# RCMX_Rev_00_BPS2.net
KiCad netlist of a schematic drawn in EAGLE
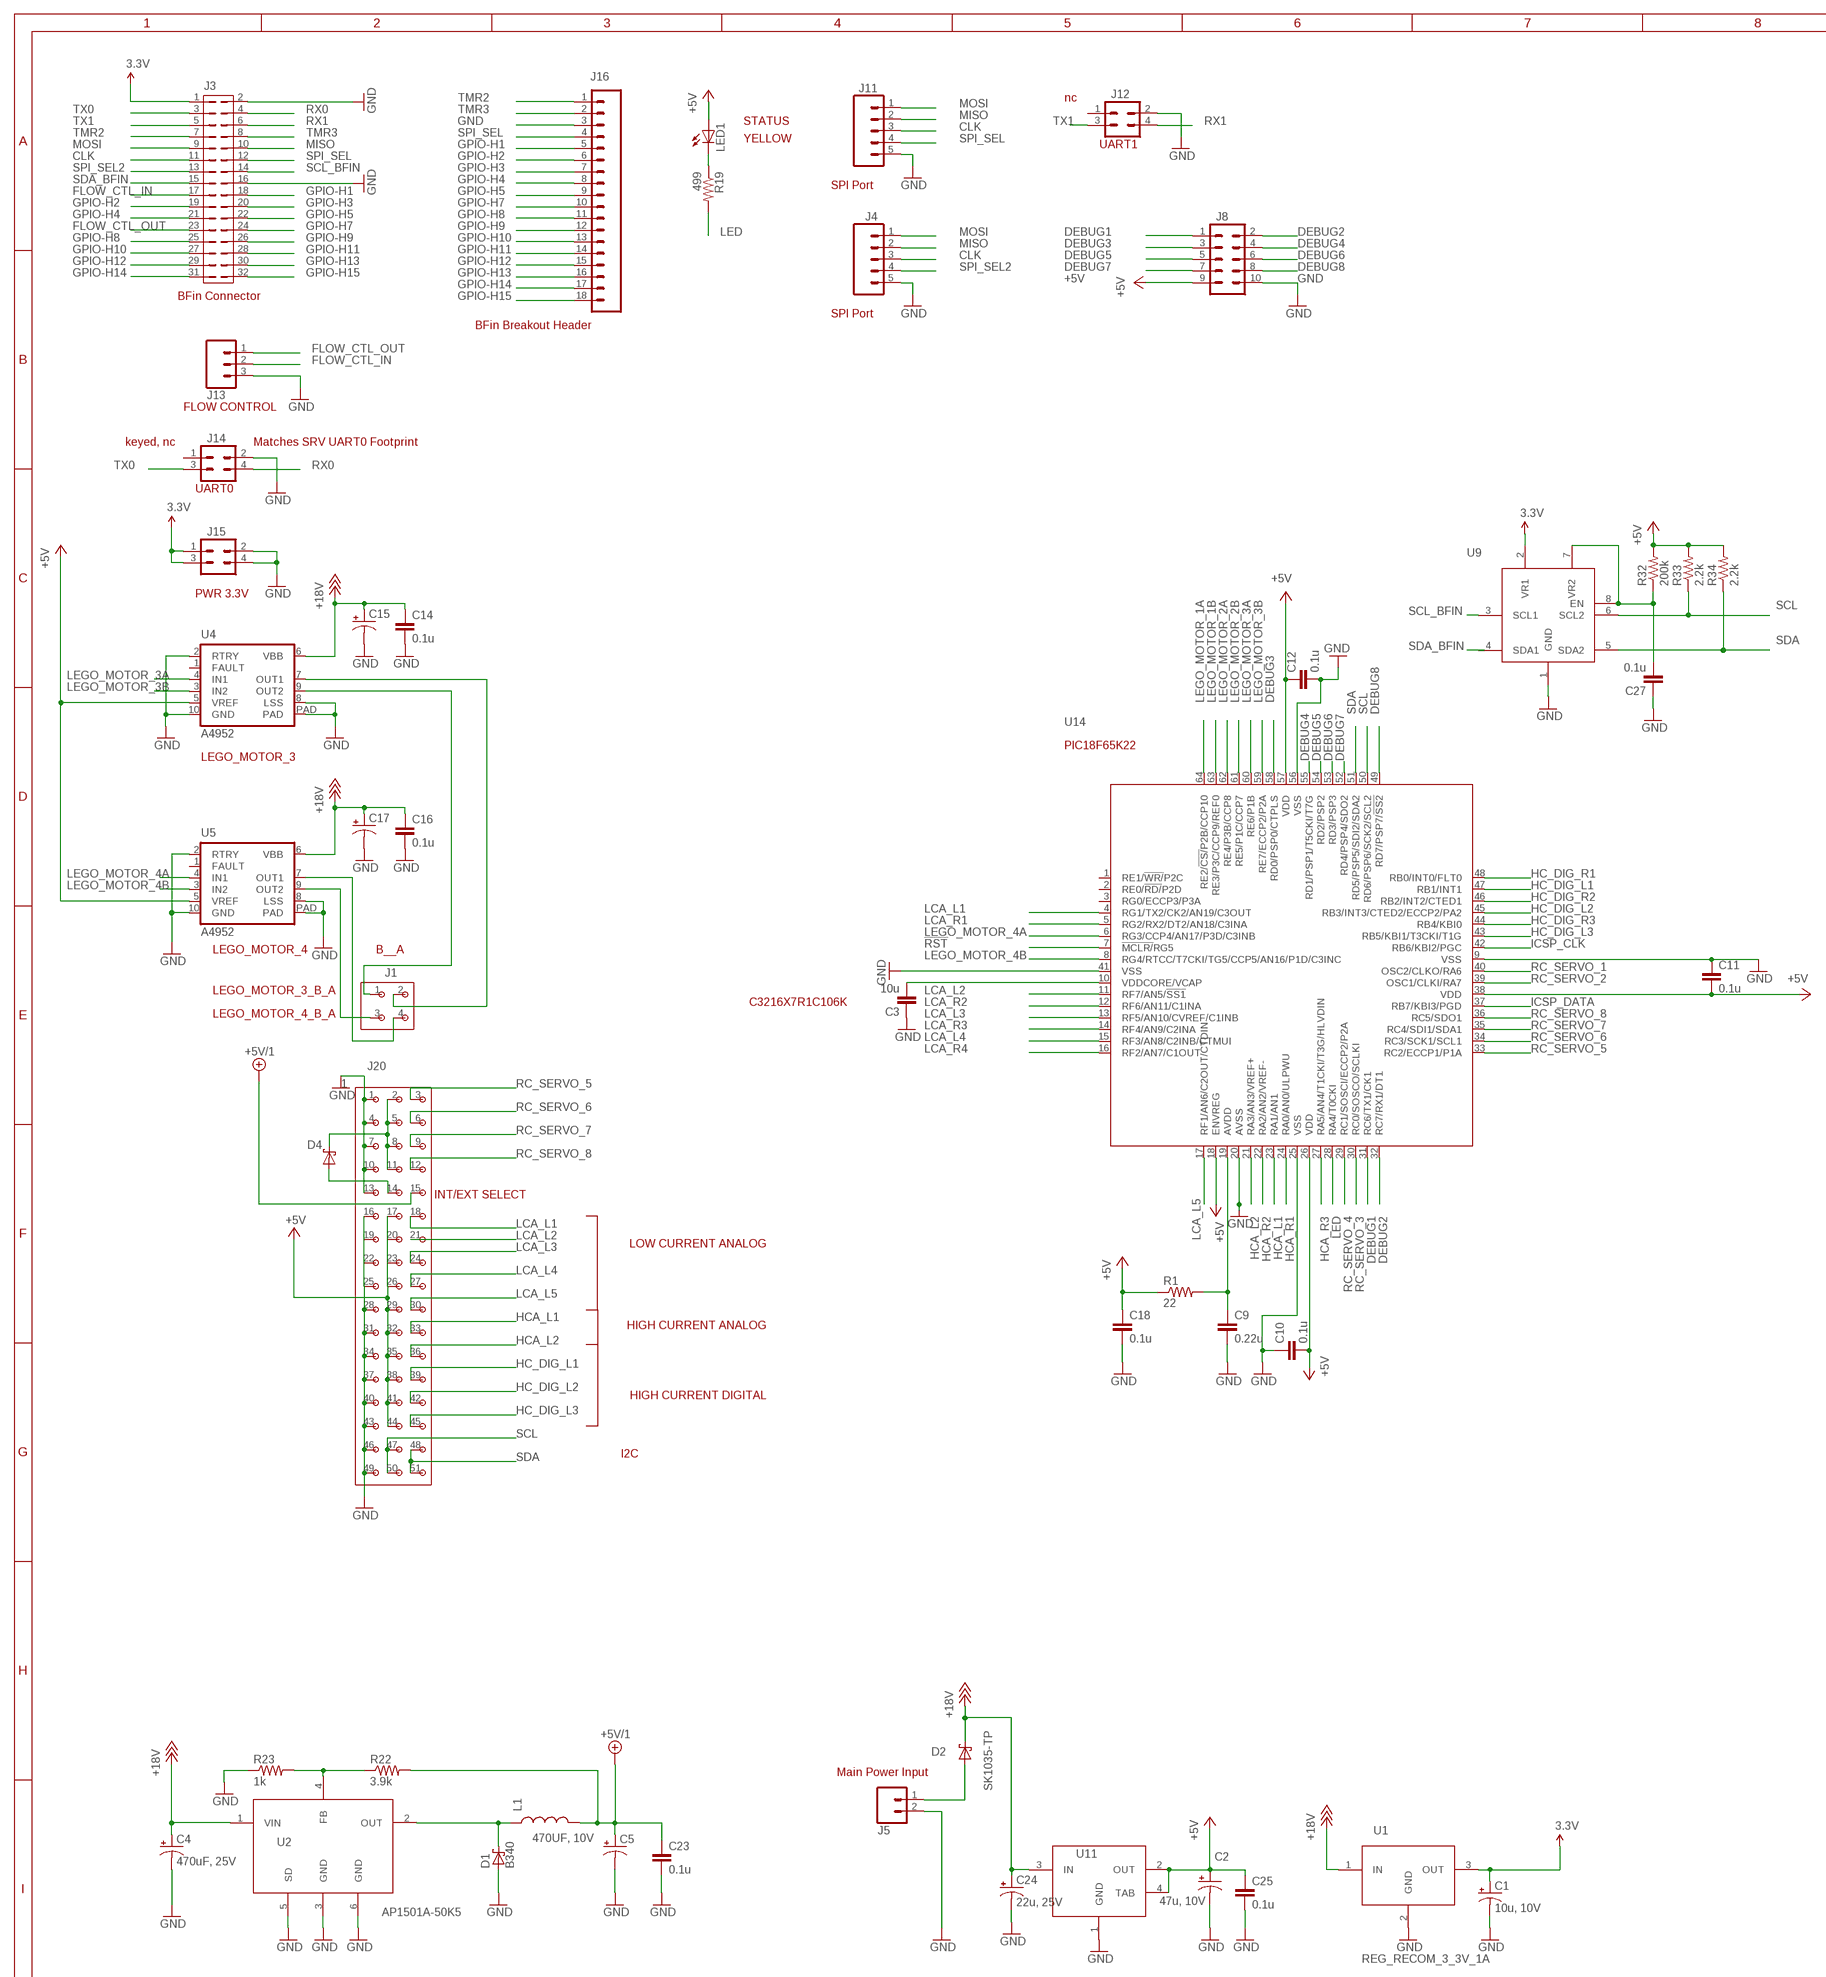
[diagram p0: schematic, sheet 1, part 1 of 2]
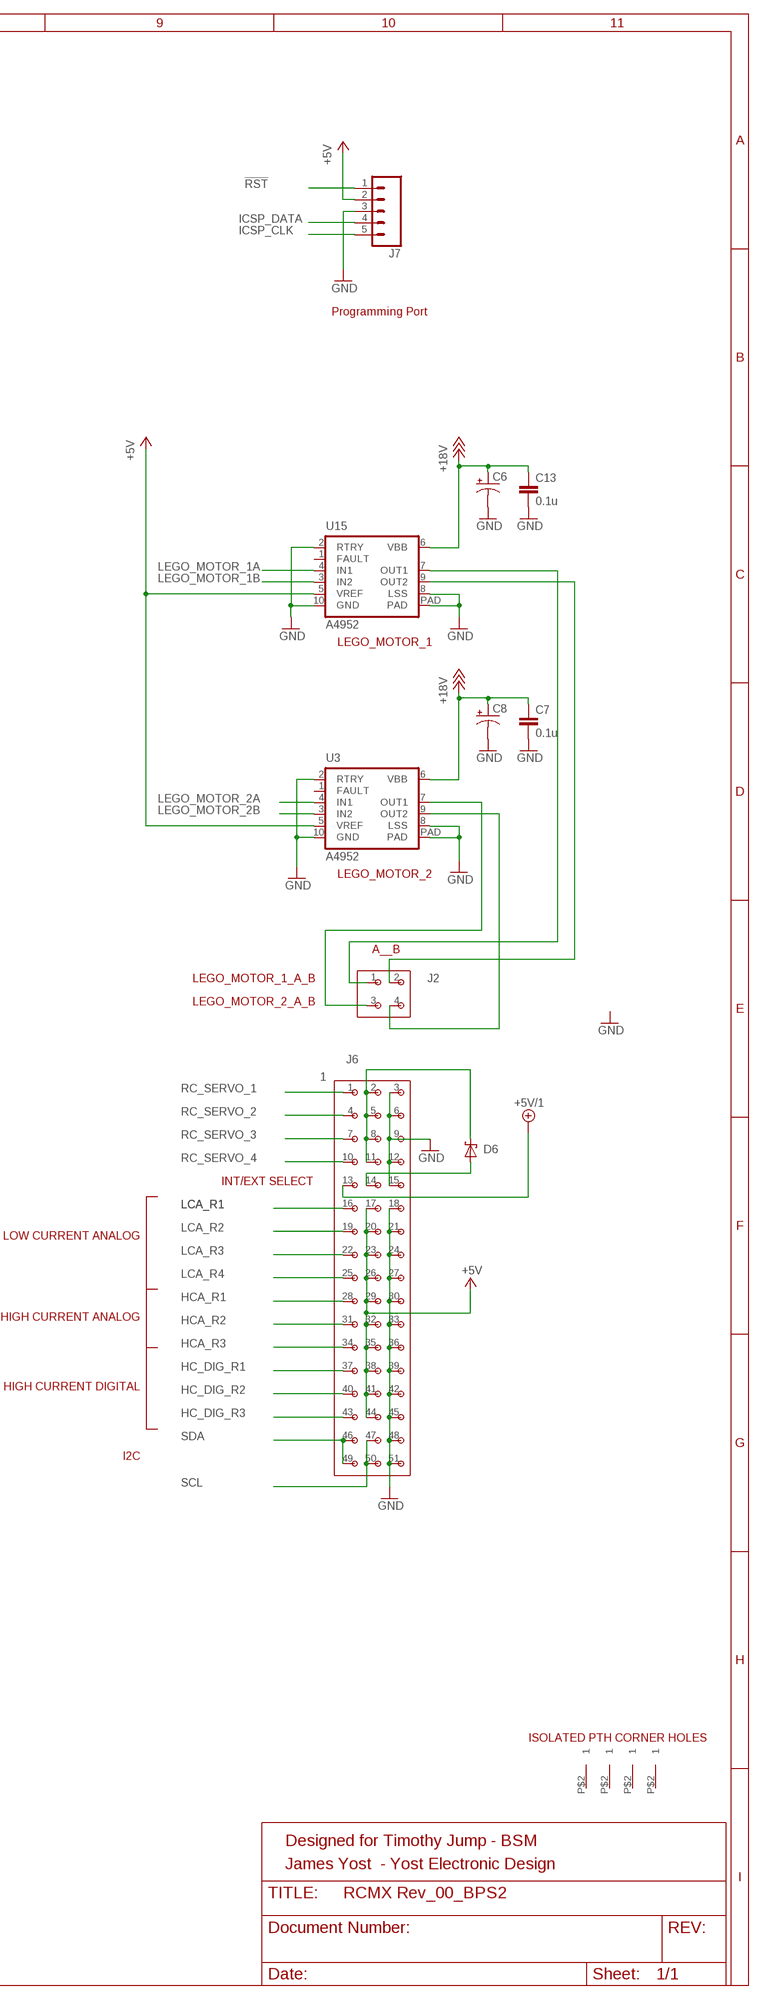
[diagram p1: schematic, sheet 1, part 2 of 2]

(export (version "E")
  (design (tool "Eeschema 10.0.6"))
  (components
    (comp (ref "C1")
      (value "10u, 10V")
      (footprint "eagle-import:EIA3216")
      (libsource (lib "eagle-import") (part "CAP_POL1206"))
    )
    (comp (ref "C2")
      (value "47u, 10V")
      (footprint "eagle-import:CAP1210_POL")
      (libsource (lib "eagle-import") (part "CAP_1210_POL"))
    )
    (comp (ref "C3")
      (value "10u")
      (footprint "eagle-import:1206")
      (libsource (lib "eagle-import") (part "CAP1206"))
    )
    (comp (ref "C4")
      (value "470uF, 25V")
      (footprint "eagle-import:PANASONIC_G")
      (libsource (lib "eagle-import") (part "CAP_POLG"))
    )
    (comp (ref "C5")
      (value "470UF, 10V")
      (footprint "eagle-import:PANASONIC_F")
      (libsource (lib "eagle-import") (part "CAP_ELT_PANASONIC_470UF"))
    )
    (comp (ref "C6")
      (value "CAP_POLD")
      (footprint "eagle-import:PANASONIC_D")
      (libsource (lib "eagle-import") (part "CAP_POLD"))
    )
    (comp (ref "C7")
      (value "0.1u")
      (footprint "eagle-import:0805")
      (libsource (lib "eagle-import") (part "CAP0805"))
    )
    (comp (ref "C8")
      (value "CAP_POLD")
      (footprint "eagle-import:PANASONIC_D")
      (libsource (lib "eagle-import") (part "CAP_POLD"))
    )
    (comp (ref "C9")
      (value "0.22u")
      (footprint "eagle-import:0805")
      (libsource (lib "eagle-import") (part "CAP0805"))
    )
    (comp (ref "C10")
      (value "0.1u")
      (footprint "eagle-import:0805")
      (libsource (lib "eagle-import") (part "CAP0805"))
    )
    (comp (ref "C11")
      (value "0.1u")
      (footprint "eagle-import:0805")
      (libsource (lib "eagle-import") (part "CAP0805"))
    )
    (comp (ref "C12")
      (value "0.1u")
      (footprint "eagle-import:0805")
      (libsource (lib "eagle-import") (part "CAP0805"))
    )
    (comp (ref "C13")
      (value "0.1u")
      (footprint "eagle-import:0805")
      (libsource (lib "eagle-import") (part "CAP0805"))
    )
    (comp (ref "C14")
      (value "0.1u")
      (footprint "eagle-import:0805")
      (libsource (lib "eagle-import") (part "CAP0805"))
    )
    (comp (ref "C15")
      (value "CAP_POLD")
      (footprint "eagle-import:PANASONIC_D")
      (libsource (lib "eagle-import") (part "CAP_POLD"))
    )
    (comp (ref "C16")
      (value "0.1u")
      (footprint "eagle-import:0805")
      (libsource (lib "eagle-import") (part "CAP0805"))
    )
    (comp (ref "C17")
      (value "CAP_POLD")
      (footprint "eagle-import:PANASONIC_D")
      (libsource (lib "eagle-import") (part "CAP_POLD"))
    )
    (comp (ref "C18")
      (value "0.1u")
      (footprint "eagle-import:0805")
      (libsource (lib "eagle-import") (part "CAP0805"))
    )
    (comp (ref "C23")
      (value "0.1u")
      (footprint "eagle-import:0805")
      (libsource (lib "eagle-import") (part "CAP0805"))
    )
    (comp (ref "C24")
      (value "22u, 25V")
      (footprint "eagle-import:CAP1210_POL")
      (libsource (lib "eagle-import") (part "CAP_1210_POL"))
    )
    (comp (ref "C25")
      (value "0.1u")
      (footprint "eagle-import:0805")
      (libsource (lib "eagle-import") (part "CAP0805"))
    )
    (comp (ref "C27")
      (value "0.1u")
      (footprint "eagle-import:0805")
      (libsource (lib "eagle-import") (part "CAP0805"))
    )
    (comp (ref "D1")
      (value "B340")
      (footprint "eagle-import:SMA_DO214AC")
      (libsource (lib "eagle-import") (part "B340"))
    )
    (comp (ref "D2")
      (value "SK1035-TP")
      (footprint "eagle-import:DO214AB")
      (libsource (lib "eagle-import") (part "SK1035-TP"))
    )
    (comp (ref "D4")
      (value "SK1035-TP")
      (footprint "eagle-import:DO214AB")
      (libsource (lib "eagle-import") (part "SK1035-TP"))
    )
    (comp (ref "D6")
      (value "SK1035-TP")
      (footprint "eagle-import:DO214AB")
      (libsource (lib "eagle-import") (part "SK1035-TP"))
    )
    (comp (ref "J1")
      (value "CON_2X2_0_100")
      (footprint "eagle-import:CON_2X2_0_100")
      (libsource (lib "eagle-import") (part "CON_2X2_0_100"))
    )
    (comp (ref "J2")
      (value "CON_2X2_0_100")
      (footprint "eagle-import:CON_2X2_0_100")
      (libsource (lib "eagle-import") (part "CON_2X2_0_100"))
    )
    (comp (ref "J3")
      (value "CON_2X16_0_100")
      (footprint "eagle-import:CON_2X16_0_100")
      (libsource (lib "eagle-import") (part "CON_2X16_0_100"))
    )
    (comp (ref "J4")
      (value "M05PTH")
      (footprint "eagle-import:1X05")
      (libsource (lib "eagle-import") (part "M05PTH"))
    )
    (comp (ref "J5")
      (value "M02NG")
      (footprint "eagle-import:1X02")
      (libsource (lib "eagle-import") (part "M02NG"))
    )
    (comp (ref "J6")
      (value "CON_3X17_0_100")
      (footprint "eagle-import:CON_3X17_0_100")
      (libsource (lib "eagle-import") (part "CON_3X17_0_100"))
    )
    (comp (ref "J7")
      (value "M05PTH")
      (footprint "eagle-import:1X05")
      (libsource (lib "eagle-import") (part "SparkFun-Connectors_M05PTH"))
    )
    (comp (ref "J8")
      (value "M05X2PTH")
      (footprint "eagle-import:AVR_ICSP")
      (libsource (lib "eagle-import") (part "M05X2PTH"))
    )
    (comp (ref "J11")
      (value "M05PTH")
      (footprint "eagle-import:1X05")
      (libsource (lib "eagle-import") (part "M05PTH"))
    )
    (comp (ref "J12")
      (value "CON2X2")
      (footprint "eagle-import:CON2X2")
      (libsource (lib "eagle-import") (part "CON2X2"))
    )
    (comp (ref "J13")
      (value "M03PTH")
      (footprint "eagle-import:1X03")
      (libsource (lib "eagle-import") (part "M03PTH"))
    )
    (comp (ref "J14")
      (value "CON2X2")
      (footprint "eagle-import:CON2X2")
      (libsource (lib "eagle-import") (part "CON2X2"))
    )
    (comp (ref "J15")
      (value "CON2X2")
      (footprint "eagle-import:CON2X2")
      (libsource (lib "eagle-import") (part "CON2X2"))
    )
    (comp (ref "J16")
      (value "CON1X18")
      (footprint "eagle-import:CON1X18")
      (libsource (lib "eagle-import") (part "CON1X18"))
    )
    (comp (ref "J20")
      (value "CON_3X17_0_100")
      (footprint "eagle-import:CON_3X17_0_100")
      (libsource (lib "eagle-import") (part "CON_3X17_0_100"))
    )
    (comp (ref "L1")
      (value "IND_47UH_COILTRONICS_2_95A")
      (footprint "eagle-import:IND_PADS_SMT")
      (libsource (lib "eagle-import") (part "IND_47UH_COILTRONICS_2_95A"))
    )
    (comp (ref "LED1")
      (value "LEDCHIP-LED0805")
      (footprint "eagle-import:CHIP-LED0805")
      (libsource (lib "eagle-import") (part "LEDCHIP-LED0805"))
    )
    (comp (ref "R1")
      (value "22")
      (footprint "eagle-import:0805")
      (libsource (lib "eagle-import") (part "RESISTOR"))
    )
    (comp (ref "R19")
      (value "499")
      (footprint "eagle-import:0805")
      (libsource (lib "eagle-import") (part "RESISTOR"))
    )
    (comp (ref "R22")
      (value "3.9k")
      (footprint "eagle-import:0805")
      (libsource (lib "eagle-import") (part "RESISTOR"))
    )
    (comp (ref "R23")
      (value "1k")
      (footprint "eagle-import:0805")
      (libsource (lib "eagle-import") (part "RESISTOR"))
    )
    (comp (ref "R32")
      (value "200k")
      (footprint "eagle-import:0805")
      (libsource (lib "eagle-import") (part "RESISTOR"))
    )
    (comp (ref "R33")
      (value "2.2k")
      (footprint "eagle-import:0805")
      (libsource (lib "eagle-import") (part "RESISTOR"))
    )
    (comp (ref "R34")
      (value "2.2k")
      (footprint "eagle-import:0805")
      (libsource (lib "eagle-import") (part "RESISTOR"))
    )
    (comp (ref "U$1")
      (value "GNDPAD")
      (footprint "eagle-import:GNDPAD")
      (libsource (lib "eagle-import") (part "GNDPAD"))
    )
    (comp (ref "U$2")
      (value "GNDPAD")
      (footprint "eagle-import:GNDPAD")
      (libsource (lib "eagle-import") (part "GNDPAD"))
    )
    (comp (ref "U$7")
      (value "GNDPAD")
      (footprint "eagle-import:GNDPAD")
      (libsource (lib "eagle-import") (part "GNDPAD"))
    )
    (comp (ref "U$8")
      (value "GNDPAD")
      (footprint "eagle-import:GNDPAD")
      (libsource (lib "eagle-import") (part "GNDPAD"))
    )
    (comp (ref "U1")
      (value "REG_RECOM_3_3V_1A")
      (footprint "eagle-import:REG_RECOM_3_3V_1A")
      (libsource (lib "eagle-import") (part "REG_RECOM_3_3V_1A"))
    )
    (comp (ref "U2")
      (value "AP1501A-50K5")
      (footprint "eagle-import:TO263-5")
      (libsource (lib "eagle-import") (part "AP1501A-50K5"))
    )
    (comp (ref "U3")
      (value "A4952")
      (footprint "eagle-import:MSOP10_W_THERMAL_PAD")
      (libsource (lib "eagle-import") (part "A4952"))
    )
    (comp (ref "U4")
      (value "A4952")
      (footprint "eagle-import:MSOP10_W_THERMAL_PAD")
      (libsource (lib "eagle-import") (part "A4952"))
    )
    (comp (ref "U5")
      (value "A4952")
      (footprint "eagle-import:MSOP10_W_THERMAL_PAD")
      (libsource (lib "eagle-import") (part "A4952"))
    )
    (comp (ref "U9")
      (value "PCA9306DCT")
      (footprint "eagle-import:TEST08")
      (libsource (lib "eagle-import") (part "PCA9306DCT"))
    )
    (comp (ref "U11")
      (value "TLV1117-5")
      (footprint "eagle-import:SOT223")
      (libsource (lib "eagle-import") (part "TLV1117-5"))
    )
    (comp (ref "U14")
      (value "MICRO_C_PIC18F65K22")
      (footprint "eagle-import:64PIN_TQFP_10X10X1MM")
      (libsource (lib "eagle-import") (part "MICRO_C_PIC18F65K22"))
    )
    (comp (ref "U15")
      (value "A4952")
      (footprint "eagle-import:MSOP10_W_THERMAL_PAD")
      (libsource (lib "eagle-import") (part "A4952"))
    )
  )
  (nets
    (net (code "1") (name "+5V") (class "Default")
      (node (ref "C10") (pin "2") (pinfunction "2_2") (pintype "passive"))
      (node (ref "C11") (pin "2") (pinfunction "2_2") (pintype "passive"))
      (node (ref "C12") (pin "1") (pinfunction "1_1") (pintype "passive"))
      (node (ref "C18") (pin "1") (pinfunction "1_1") (pintype "passive"))
      (node (ref "C2") (pin "1") (pinfunction "+_1") (pintype "passive"))
      (node (ref "C25") (pin "1") (pinfunction "1_1") (pintype "passive"))
      (node (ref "J20") (pin "17") (pinfunction "17_17") (pintype "passive"))
      (node (ref "J20") (pin "20") (pinfunction "20_20") (pintype "passive"))
      (node (ref "J20") (pin "23") (pinfunction "23_23") (pintype "passive"))
      (node (ref "J20") (pin "26") (pinfunction "26_26") (pintype "passive"))
      (node (ref "J20") (pin "29") (pinfunction "29_29") (pintype "passive"))
      (node (ref "J20") (pin "32") (pinfunction "32_32") (pintype "passive"))
      (node (ref "J20") (pin "35") (pinfunction "35_35") (pintype "passive"))
      (node (ref "J20") (pin "38") (pinfunction "38_38") (pintype "passive"))
      (node (ref "J20") (pin "41") (pinfunction "41_41") (pintype "passive"))
      (node (ref "J20") (pin "44") (pinfunction "44_44") (pintype "passive"))
      (node (ref "J6") (pin "17") (pinfunction "17_17") (pintype "passive"))
      (node (ref "J6") (pin "20") (pinfunction "20_20") (pintype "passive"))
      (node (ref "J6") (pin "23") (pinfunction "23_23") (pintype "passive"))
      (node (ref "J6") (pin "26") (pinfunction "26_26") (pintype "passive"))
      (node (ref "J6") (pin "29") (pinfunction "29_29") (pintype "passive"))
      (node (ref "J6") (pin "32") (pinfunction "32_32") (pintype "passive"))
      (node (ref "J6") (pin "35") (pinfunction "35_35") (pintype "passive"))
      (node (ref "J6") (pin "38") (pinfunction "38_38") (pintype "passive"))
      (node (ref "J6") (pin "41") (pinfunction "41_41") (pintype "passive"))
      (node (ref "J6") (pin "44") (pinfunction "44_44") (pintype "passive"))
      (node (ref "J7") (pin "2") (pinfunction "2_2") (pintype "passive"))
      (node (ref "J8") (pin "9") (pinfunction "9_9") (pintype "passive"))
      (node (ref "LED1") (pin "A") (pinfunction "A_A") (pintype "passive"))
      (node (ref "R1") (pin "1") (pinfunction "1_1") (pintype "passive"))
      (node (ref "R32") (pin "2") (pinfunction "2_2") (pintype "passive"))
      (node (ref "R33") (pin "2") (pinfunction "2_2") (pintype "passive"))
      (node (ref "R34") (pin "2") (pinfunction "2_2") (pintype "passive"))
      (node (ref "U11") (pin "2") (pinfunction "OUT_2") (pintype "bidirectional"))
      (node (ref "U11") (pin "4") (pinfunction "TAB_4") (pintype "bidirectional"))
      (node (ref "U14") (pin "18") (pinfunction "ENVREG_18") (pintype "input"))
      (node (ref "U14") (pin "26") (pinfunction "VDD_26") (pintype "power_in"))
      (node (ref "U14") (pin "38") (pinfunction "VDD_38") (pintype "power_in"))
      (node (ref "U14") (pin "57") (pinfunction "VDD_57") (pintype "power_in"))
      (node (ref "U15") (pin "5") (pinfunction "VREF_5") (pintype "passive"))
      (node (ref "U3") (pin "5") (pinfunction "VREF_5") (pintype "passive"))
      (node (ref "U4") (pin "5") (pinfunction "VREF_5") (pintype "passive"))
      (node (ref "U5") (pin "5") (pinfunction "VREF_5") (pintype "passive"))
    )
    (net (code "2") (name "+5V{slash}1") (class "Default")
      (node (ref "C23") (pin "1") (pinfunction "1_1") (pintype "passive"))
      (node (ref "C5") (pin "+") (pinfunction "+_+") (pintype "passive"))
      (node (ref "J20") (pin "15") (pinfunction "15_15") (pintype "passive"))
      (node (ref "J6") (pin "13") (pinfunction "13_13") (pintype "passive"))
      (node (ref "L1") (pin "2") (pinfunction "2_2") (pintype "passive"))
      (node (ref "R22") (pin "2") (pinfunction "2_2") (pintype "passive"))
    )
    (net (code "3") (name "+18V") (class "Default")
      (node (ref "C13") (pin "1") (pinfunction "1_1") (pintype "passive"))
      (node (ref "C14") (pin "1") (pinfunction "1_1") (pintype "passive"))
      (node (ref "C15") (pin "+") (pinfunction "+_+") (pintype "passive"))
      (node (ref "C16") (pin "1") (pinfunction "1_1") (pintype "passive"))
      (node (ref "C17") (pin "+") (pinfunction "+_+") (pintype "passive"))
      (node (ref "C24") (pin "1") (pinfunction "+_1") (pintype "passive"))
      (node (ref "C4") (pin "+") (pinfunction "+_+") (pintype "passive"))
      (node (ref "C6") (pin "+") (pinfunction "+_+") (pintype "passive"))
      (node (ref "C7") (pin "1") (pinfunction "1_1") (pintype "passive"))
      (node (ref "C8") (pin "+") (pinfunction "+_+") (pintype "passive"))
      (node (ref "D2") (pin "1") (pinfunction "C_1") (pintype "passive"))
      (node (ref "U1") (pin "1") (pinfunction "IN_1") (pintype "bidirectional"))
      (node (ref "U11") (pin "3") (pinfunction "IN_3") (pintype "bidirectional"))
      (node (ref "U15") (pin "6") (pinfunction "VBB_6") (pintype "input"))
      (node (ref "U2") (pin "1") (pinfunction "VIN_1") (pintype "bidirectional"))
      (node (ref "U3") (pin "6") (pinfunction "VBB_6") (pintype "input"))
      (node (ref "U4") (pin "6") (pinfunction "VBB_6") (pintype "input"))
      (node (ref "U5") (pin "6") (pinfunction "VBB_6") (pintype "input"))
    )
    (net (code "4") (name "/CLK") (class "Default")
      (node (ref "J11") (pin "3") (pinfunction "3_3") (pintype "passive"))
      (node (ref "J3") (pin "11") (pinfunction "11_11") (pintype "passive"))
      (node (ref "J4") (pin "3") (pinfunction "3_3") (pintype "passive"))
    )
    (net (code "5") (name "/DEBUG1") (class "Default")
      (node (ref "J8") (pin "1") (pinfunction "1_1") (pintype "passive"))
      (node (ref "U14") (pin "31") (pinfunction "RC6/TX1/CK1_31") (pintype "bidirectional"))
    )
    (net (code "6") (name "/DEBUG2") (class "Default")
      (node (ref "J8") (pin "2") (pinfunction "2_2") (pintype "passive"))
      (node (ref "U14") (pin "32") (pinfunction "RC7/RX1/DT1_32") (pintype "bidirectional"))
    )
    (net (code "7") (name "/DEBUG3") (class "Default")
      (node (ref "J8") (pin "3") (pinfunction "3_3") (pintype "passive"))
      (node (ref "U14") (pin "58") (pinfunction "RD0/PSP0/CTPLS_58") (pintype "bidirectional"))
    )
    (net (code "8") (name "/DEBUG4") (class "Default")
      (node (ref "J8") (pin "4") (pinfunction "4_4") (pintype "passive"))
      (node (ref "U14") (pin "55") (pinfunction "RD1/PSP1/T5CKI/T7G_55") (pintype "bidirectional"))
    )
    (net (code "9") (name "/DEBUG5") (class "Default")
      (node (ref "J8") (pin "5") (pinfunction "5_5") (pintype "passive"))
      (node (ref "U14") (pin "54") (pinfunction "RD2/PSP2_54") (pintype "bidirectional"))
    )
    (net (code "10") (name "/DEBUG6") (class "Default")
      (node (ref "J8") (pin "6") (pinfunction "6_6") (pintype "passive"))
      (node (ref "U14") (pin "53") (pinfunction "RD3/PSP3_53") (pintype "bidirectional"))
    )
    (net (code "11") (name "/DEBUG7") (class "Default")
      (node (ref "J8") (pin "7") (pinfunction "7_7") (pintype "passive"))
      (node (ref "U14") (pin "52") (pinfunction "RD4/PSP4/SDO2_52") (pintype "bidirectional"))
    )
    (net (code "12") (name "/DEBUG8") (class "Default")
      (node (ref "J8") (pin "8") (pinfunction "8_8") (pintype "passive"))
      (node (ref "U14") (pin "49") (pinfunction "RD7/PSP7/~{SS2}_49") (pintype "bidirectional"))
    )
    (net (code "13") (name "/FLOW_CTL_IN") (class "Default")
      (node (ref "J13") (pin "2") (pinfunction "2_2") (pintype "passive"))
      (node (ref "J3") (pin "17") (pinfunction "17_17") (pintype "passive"))
    )
    (net (code "14") (name "/FLOW_CTL_OUT") (class "Default")
      (node (ref "J13") (pin "1") (pinfunction "1_1") (pintype "passive"))
      (node (ref "J3") (pin "23") (pinfunction "23_23") (pintype "passive"))
    )
    (net (code "15") (name "/GPIO-H1") (class "Default")
      (node (ref "J16") (pin "5") (pinfunction "5_5") (pintype "passive"))
      (node (ref "J3") (pin "18") (pinfunction "18_18") (pintype "passive"))
    )
    (net (code "16") (name "/GPIO-H2") (class "Default")
      (node (ref "J16") (pin "6") (pinfunction "6_6") (pintype "passive"))
      (node (ref "J3") (pin "19") (pinfunction "19_19") (pintype "passive"))
    )
    (net (code "17") (name "/GPIO-H3") (class "Default")
      (node (ref "J16") (pin "7") (pinfunction "7_7") (pintype "passive"))
      (node (ref "J3") (pin "20") (pinfunction "20_20") (pintype "passive"))
    )
    (net (code "18") (name "/GPIO-H4") (class "Default")
      (node (ref "J16") (pin "8") (pinfunction "8_8") (pintype "passive"))
      (node (ref "J3") (pin "21") (pinfunction "21_21") (pintype "passive"))
    )
    (net (code "19") (name "/GPIO-H5") (class "Default")
      (node (ref "J16") (pin "9") (pinfunction "9_9") (pintype "passive"))
      (node (ref "J3") (pin "22") (pinfunction "22_22") (pintype "passive"))
    )
    (net (code "20") (name "/GPIO-H7") (class "Default")
      (node (ref "J16") (pin "10") (pinfunction "10_10") (pintype "passive"))
      (node (ref "J3") (pin "24") (pinfunction "24_24") (pintype "passive"))
    )
    (net (code "21") (name "/GPIO-H8") (class "Default")
      (node (ref "J16") (pin "11") (pinfunction "11_11") (pintype "passive"))
      (node (ref "J3") (pin "25") (pinfunction "25_25") (pintype "passive"))
    )
    (net (code "22") (name "/GPIO-H9") (class "Default")
      (node (ref "J16") (pin "12") (pinfunction "12_12") (pintype "passive"))
      (node (ref "J3") (pin "26") (pinfunction "26_26") (pintype "passive"))
    )
    (net (code "23") (name "/GPIO-H10") (class "Default")
      (node (ref "J16") (pin "13") (pinfunction "13_13") (pintype "passive"))
      (node (ref "J3") (pin "27") (pinfunction "27_27") (pintype "passive"))
    )
    (net (code "24") (name "/GPIO-H11") (class "Default")
      (node (ref "J16") (pin "14") (pinfunction "14_14") (pintype "passive"))
      (node (ref "J3") (pin "28") (pinfunction "28_28") (pintype "passive"))
    )
    (net (code "25") (name "/GPIO-H12") (class "Default")
      (node (ref "J16") (pin "15") (pinfunction "15_15") (pintype "passive"))
      (node (ref "J3") (pin "29") (pinfunction "29_29") (pintype "passive"))
    )
    (net (code "26") (name "/GPIO-H13") (class "Default")
      (node (ref "J16") (pin "16") (pinfunction "16_16") (pintype "passive"))
      (node (ref "J3") (pin "30") (pinfunction "30_30") (pintype "passive"))
    )
    (net (code "27") (name "/GPIO-H14") (class "Default")
      (node (ref "J16") (pin "17") (pinfunction "17_17") (pintype "passive"))
      (node (ref "J3") (pin "31") (pinfunction "31_31") (pintype "passive"))
    )
    (net (code "28") (name "/GPIO-H15") (class "Default")
      (node (ref "J16") (pin "18") (pinfunction "18_18") (pintype "passive"))
      (node (ref "J3") (pin "32") (pinfunction "32_32") (pintype "passive"))
    )
    (net (code "29") (name "/HCA_L1") (class "Default")
      (node (ref "J20") (pin "33") (pinfunction "33_33") (pintype "passive"))
      (node (ref "U14") (pin "23") (pinfunction "RA1/AN1_23") (pintype "bidirectional"))
    )
    (net (code "30") (name "/HCA_L2") (class "Default")
      (node (ref "J20") (pin "36") (pinfunction "36_36") (pintype "passive"))
      (node (ref "U14") (pin "21") (pinfunction "RA3/AN3/VREF+_21") (pintype "bidirectional"))
    )
    (net (code "31") (name "/HCA_R1") (class "Default")
      (node (ref "J6") (pin "28") (pinfunction "28_28") (pintype "passive"))
      (node (ref "U14") (pin "24") (pinfunction "RA0/AN0/ULPWU_24") (pintype "bidirectional"))
    )
    (net (code "32") (name "/HCA_R2") (class "Default")
      (node (ref "J6") (pin "31") (pinfunction "31_31") (pintype "passive"))
      (node (ref "U14") (pin "22") (pinfunction "RA2/AN2/VREF-_22") (pintype "bidirectional"))
    )
    (net (code "33") (name "/HCA_R3") (class "Default")
      (node (ref "J6") (pin "34") (pinfunction "34_34") (pintype "passive"))
      (node (ref "U14") (pin "27") (pinfunction "RA5/AN4/T1CKI/T3G/HLVDIN_27") (pintype "bidirectional"))
    )
    (net (code "34") (name "/HC_DIG_L1") (class "Default")
      (node (ref "J20") (pin "39") (pinfunction "39_39") (pintype "passive"))
      (node (ref "U14") (pin "47") (pinfunction "RB1/INT1_47") (pintype "bidirectional"))
    )
    (net (code "35") (name "/HC_DIG_L2") (class "Default")
      (node (ref "J20") (pin "42") (pinfunction "42_42") (pintype "passive"))
      (node (ref "U14") (pin "45") (pinfunction "RB3/INT3/CTED2/ECCP2/PA2_45") (pintype "bidirectional"))
    )
    (net (code "36") (name "/HC_DIG_L3") (class "Default")
      (node (ref "J20") (pin "45") (pinfunction "45_45") (pintype "passive"))
      (node (ref "U14") (pin "43") (pinfunction "RB5/KBI1/T3CKI/T1G_43") (pintype "bidirectional"))
    )
    (net (code "37") (name "/HC_DIG_R1") (class "Default")
      (node (ref "J6") (pin "37") (pinfunction "37_37") (pintype "passive"))
      (node (ref "U14") (pin "48") (pinfunction "RB0/INT0/FLT0_48") (pintype "bidirectional"))
    )
    (net (code "38") (name "/HC_DIG_R2") (class "Default")
      (node (ref "J6") (pin "40") (pinfunction "40_40") (pintype "passive"))
      (node (ref "U14") (pin "46") (pinfunction "RB2/INT2/CTED1_46") (pintype "bidirectional"))
    )
    (net (code "39") (name "/HC_DIG_R3") (class "Default")
      (node (ref "J6") (pin "43") (pinfunction "43_43") (pintype "passive"))
      (node (ref "U14") (pin "44") (pinfunction "RB4/KBI0_44") (pintype "bidirectional"))
    )
    (net (code "40") (name "/ICSP_CLK") (class "Default")
      (node (ref "J7") (pin "5") (pinfunction "5_5") (pintype "passive"))
      (node (ref "U14") (pin "42") (pinfunction "RB6/KBI2/PGC_42") (pintype "bidirectional"))
    )
    (net (code "41") (name "/ICSP_DATA") (class "Default")
      (node (ref "J7") (pin "4") (pinfunction "4_4") (pintype "passive"))
      (node (ref "U14") (pin "37") (pinfunction "RB7/KBI3/PGD_37") (pintype "bidirectional"))
    )
    (net (code "42") (name "/LCA_L1") (class "Default")
      (node (ref "J20") (pin "18") (pinfunction "18_18") (pintype "passive"))
      (node (ref "U14") (pin "4") (pinfunction "RG1/TX2/CK2/AN19/C3OUT_4") (pintype "bidirectional"))
    )
    (net (code "43") (name "/LCA_L2") (class "Default")
      (node (ref "J20") (pin "21") (pinfunction "21_21") (pintype "passive"))
      (node (ref "U14") (pin "11") (pinfunction "RF7/AN5/~{SS1}_11") (pintype "bidirectional"))
    )
    (net (code "44") (name "/LCA_L3") (class "Default")
      (node (ref "J20") (pin "24") (pinfunction "24_24") (pintype "passive"))
      (node (ref "U14") (pin "13") (pinfunction "RF5/AN10/CVREF/C1INB_13") (pintype "bidirectional"))
    )
    (net (code "45") (name "/LCA_L4") (class "Default")
      (node (ref "J20") (pin "27") (pinfunction "27_27") (pintype "passive"))
      (node (ref "U14") (pin "15") (pinfunction "RF3/AN8/C2INB/CTMUI_15") (pintype "bidirectional"))
    )
    (net (code "46") (name "/LCA_L5") (class "Default")
      (node (ref "J20") (pin "30") (pinfunction "30_30") (pintype "passive"))
      (node (ref "U14") (pin "17") (pinfunction "RF1/AN6/C2OUT/CTDIN_17") (pintype "bidirectional"))
    )
    (net (code "47") (name "/LCA_R1") (class "Default")
      (node (ref "J6") (pin "16") (pinfunction "16_16") (pintype "passive"))
      (node (ref "U14") (pin "5") (pinfunction "RG2/RX2/DT2/AN18/C3INA_5") (pintype "bidirectional"))
    )
    (net (code "48") (name "/LCA_R2") (class "Default")
      (node (ref "J6") (pin "19") (pinfunction "19_19") (pintype "passive"))
      (node (ref "U14") (pin "12") (pinfunction "RF6/AN11/C1INA_12") (pintype "bidirectional"))
    )
    (net (code "49") (name "/LCA_R3") (class "Default")
      (node (ref "J6") (pin "22") (pinfunction "22_22") (pintype "passive"))
      (node (ref "U14") (pin "14") (pinfunction "RF4/AN9/C2INA_14") (pintype "bidirectional"))
    )
    (net (code "50") (name "/LCA_R4") (class "Default")
      (node (ref "J6") (pin "25") (pinfunction "25_25") (pintype "passive"))
      (node (ref "U14") (pin "16") (pinfunction "RF2/AN7/C1OUT_16") (pintype "bidirectional"))
    )
    (net (code "51") (name "/LED") (class "Default")
      (node (ref "R19") (pin "2") (pinfunction "2_2") (pintype "passive"))
      (node (ref "U14") (pin "28") (pinfunction "RA4/T0CKI_28") (pintype "bidirectional"))
    )
    (net (code "52") (name "/LEGO_MOTOR_1A") (class "Default")
      (node (ref "U14") (pin "64") (pinfunction "RE2/~{CS/}P2B/CCP10_64") (pintype "bidirectional"))
      (node (ref "U15") (pin "4") (pinfunction "IN1_4") (pintype "input"))
    )
    (net (code "53") (name "/LEGO_MOTOR_1B") (class "Default")
      (node (ref "U14") (pin "63") (pinfunction "RE3/P3C/CCP9/REF0_63") (pintype "bidirectional"))
      (node (ref "U15") (pin "3") (pinfunction "IN2_3") (pintype "input"))
    )
    (net (code "54") (name "/LEGO_MOTOR_2A") (class "Default")
      (node (ref "U14") (pin "62") (pinfunction "RE4/P3B/CCP8_62") (pintype "bidirectional"))
      (node (ref "U3") (pin "4") (pinfunction "IN1_4") (pintype "input"))
    )
    (net (code "55") (name "/LEGO_MOTOR_2B") (class "Default")
      (node (ref "U14") (pin "61") (pinfunction "RE5/P1C/CCP7_61") (pintype "bidirectional"))
      (node (ref "U3") (pin "3") (pinfunction "IN2_3") (pintype "input"))
    )
    (net (code "56") (name "/LEGO_MOTOR_3A") (class "Default")
      (node (ref "U14") (pin "60") (pinfunction "RE6/P1B_60") (pintype "bidirectional"))
      (node (ref "U4") (pin "4") (pinfunction "IN1_4") (pintype "input"))
    )
    (net (code "57") (name "/LEGO_MOTOR_3B") (class "Default")
      (node (ref "U14") (pin "59") (pinfunction "RE7/ECCP2/P2A_59") (pintype "bidirectional"))
      (node (ref "U4") (pin "3") (pinfunction "IN2_3") (pintype "input"))
    )
    (net (code "58") (name "/LEGO_MOTOR_4A") (class "Default")
      (node (ref "U14") (pin "6") (pinfunction "RG3/CCP4/AN17/P3D/C3INB_6") (pintype "bidirectional"))
      (node (ref "U5") (pin "4") (pinfunction "IN1_4") (pintype "input"))
    )
    (net (code "59") (name "/LEGO_MOTOR_4B") (class "Default")
      (node (ref "U14") (pin "8") (pinfunction "RG4/RTCC/T7CKI/TG5/CCP5/AN16/P1D/C3INC_8") (pintype "bidirectional"))
      (node (ref "U5") (pin "3") (pinfunction "IN2_3") (pintype "input"))
    )
    (net (code "60") (name "/MISO") (class "Default")
      (node (ref "J11") (pin "2") (pinfunction "2_2") (pintype "passive"))
      (node (ref "J3") (pin "10") (pinfunction "10_10") (pintype "passive"))
      (node (ref "J4") (pin "2") (pinfunction "2_2") (pintype "passive"))
    )
    (net (code "61") (name "/MOSI") (class "Default")
      (node (ref "J11") (pin "1") (pinfunction "1_1") (pintype "passive"))
      (node (ref "J3") (pin "9") (pinfunction "9_9") (pintype "passive"))
      (node (ref "J4") (pin "1") (pinfunction "1_1") (pintype "passive"))
    )
    (net (code "62") (name "/RC_SERVO_1") (class "Default")
      (node (ref "J6") (pin "1") (pinfunction "1_1") (pintype "passive"))
      (node (ref "U14") (pin "40") (pinfunction "OSC2/CLKO/RA6_40") (pintype "output"))
    )
    (net (code "63") (name "/RC_SERVO_2") (class "Default")
      (node (ref "J6") (pin "4") (pinfunction "4_4") (pintype "passive"))
      (node (ref "U14") (pin "39") (pinfunction "OSC1/CLKI/RA7_39") (pintype "input"))
    )
    (net (code "64") (name "/RC_SERVO_3") (class "Default")
      (node (ref "J6") (pin "7") (pinfunction "7_7") (pintype "passive"))
      (node (ref "U14") (pin "30") (pinfunction "RC0/SOSCO/SCLKI_30") (pintype "bidirectional"))
    )
    (net (code "65") (name "/RC_SERVO_4") (class "Default")
      (node (ref "J6") (pin "10") (pinfunction "10_10") (pintype "passive"))
      (node (ref "U14") (pin "29") (pinfunction "RC1/SOSCI/ECCP2/P2A_29") (pintype "bidirectional"))
    )
    (net (code "66") (name "/RC_SERVO_5") (class "Default")
      (node (ref "J20") (pin "3") (pinfunction "3_3") (pintype "passive"))
      (node (ref "U14") (pin "33") (pinfunction "RC2/ECCP1/P1A_33") (pintype "bidirectional"))
    )
    (net (code "67") (name "/RC_SERVO_6") (class "Default")
      (node (ref "J20") (pin "6") (pinfunction "6_6") (pintype "passive"))
      (node (ref "U14") (pin "34") (pinfunction "RC3/SCK1/SCL1_34") (pintype "bidirectional"))
    )
    (net (code "68") (name "/RC_SERVO_7") (class "Default")
      (node (ref "J20") (pin "9") (pinfunction "9_9") (pintype "passive"))
      (node (ref "U14") (pin "35") (pinfunction "RC4/SDI1/SDA1_35") (pintype "bidirectional"))
    )
    (net (code "69") (name "/RC_SERVO_8") (class "Default")
      (node (ref "J20") (pin "12") (pinfunction "12_12") (pintype "passive"))
      (node (ref "U14") (pin "36") (pinfunction "RC5/SDO1_36") (pintype "bidirectional"))
    )
    (net (code "70") (name "/RX0") (class "Default")
      (node (ref "J14") (pin "4") (pinfunction "4_4") (pintype "passive"))
      (node (ref "J3") (pin "4") (pinfunction "4_4") (pintype "passive"))
    )
    (net (code "71") (name "/RX1") (class "Default")
      (node (ref "J12") (pin "4") (pinfunction "4_4") (pintype "passive"))
      (node (ref "J3") (pin "6") (pinfunction "6_6") (pintype "passive"))
    )
    (net (code "72") (name "/SCL") (class "Default")
      (node (ref "J20") (pin "47") (pinfunction "47_47") (pintype "passive"))
      (node (ref "J20") (pin "50") (pinfunction "50_50") (pintype "passive"))
      (node (ref "J6") (pin "47") (pinfunction "47_47") (pintype "passive"))
      (node (ref "J6") (pin "50") (pinfunction "50_50") (pintype "passive"))
      (node (ref "R33") (pin "1") (pinfunction "1_1") (pintype "passive"))
      (node (ref "U14") (pin "50") (pinfunction "RD6/PSP6/SCK2/SCL2_50") (pintype "bidirectional"))
      (node (ref "U9") (pin "6") (pinfunction "SCL2_6") (pintype "bidirectional"))
    )
    (net (code "73") (name "/SCL_BFIN") (class "Default")
      (node (ref "J3") (pin "14") (pinfunction "14_14") (pintype "passive"))
      (node (ref "U9") (pin "3") (pinfunction "SCL1_3") (pintype "bidirectional"))
    )
    (net (code "74") (name "/SDA") (class "Default")
      (node (ref "J20") (pin "48") (pinfunction "48_48") (pintype "passive"))
      (node (ref "J20") (pin "51") (pinfunction "51_51") (pintype "passive"))
      (node (ref "J6") (pin "46") (pinfunction "46_46") (pintype "passive"))
      (node (ref "J6") (pin "49") (pinfunction "49_49") (pintype "passive"))
      (node (ref "R34") (pin "1") (pinfunction "1_1") (pintype "passive"))
      (node (ref "U14") (pin "51") (pinfunction "RD5/PSP5/SDI2/SDA2_51") (pintype "bidirectional"))
      (node (ref "U9") (pin "5") (pinfunction "SDA2_5") (pintype "bidirectional"))
    )
    (net (code "75") (name "/SDA_BFIN") (class "Default")
      (node (ref "J3") (pin "15") (pinfunction "15_15") (pintype "passive"))
    )
    (net (code "76") (name "/SPI_SEL") (class "Default")
      (node (ref "J11") (pin "4") (pinfunction "4_4") (pintype "passive"))
      (node (ref "J16") (pin "4") (pinfunction "4_4") (pintype "passive"))
      (node (ref "J3") (pin "12") (pinfunction "12_12") (pintype "passive"))
    )
    (net (code "77") (name "/SPI_SEL2") (class "Default")
      (node (ref "J3") (pin "13") (pinfunction "13_13") (pintype "passive"))
      (node (ref "J4") (pin "4") (pinfunction "4_4") (pintype "passive"))
    )
    (net (code "78") (name "/TMR2") (class "Default")
      (node (ref "J16") (pin "1") (pinfunction "1_1") (pintype "passive"))
      (node (ref "J3") (pin "7") (pinfunction "7_7") (pintype "passive"))
    )
    (net (code "79") (name "/TMR3") (class "Default")
      (node (ref "J16") (pin "2") (pinfunction "2_2") (pintype "passive"))
      (node (ref "J3") (pin "8") (pinfunction "8_8") (pintype "passive"))
    )
    (net (code "80") (name "/TX0") (class "Default")
      (node (ref "J14") (pin "3") (pinfunction "3_3") (pintype "passive"))
      (node (ref "J3") (pin "3") (pinfunction "3_3") (pintype "passive"))
    )
    (net (code "81") (name "/TX1") (class "Default")
      (node (ref "J12") (pin "3") (pinfunction "3_3") (pintype "passive"))
      (node (ref "J3") (pin "5") (pinfunction "5_5") (pintype "passive"))
    )
    (net (code "82") (name "/~{RST}") (class "Default")
      (node (ref "J7") (pin "1") (pinfunction "1_1") (pintype "passive"))
      (node (ref "U14") (pin "7") (pinfunction "~{MCLR/}RG5_7") (pintype "input"))
    )
    (net (code "83") (name "3.3V") (class "Default")
      (node (ref "C1") (pin "A") (pinfunction "+_A") (pintype "passive"))
      (node (ref "J15") (pin "1") (pinfunction "1_1") (pintype "passive"))
      (node (ref "J15") (pin "3") (pinfunction "3_3") (pintype "passive"))
      (node (ref "J3") (pin "1") (pinfunction "1_1") (pintype "passive"))
      (node (ref "U1") (pin "3") (pinfunction "OUT_3") (pintype "bidirectional"))
      (node (ref "U9") (pin "2") (pinfunction "VR1_2") (pintype "bidirectional"))
    )
    (net (code "84") (name "GND") (class "Default")
      (node (ref "C1") (pin "C") (pinfunction "-_C") (pintype "passive"))
      (node (ref "C10") (pin "1") (pinfunction "1_1") (pintype "passive"))
      (node (ref "C11") (pin "1") (pinfunction "1_1") (pintype "passive"))
      (node (ref "C12") (pin "2") (pinfunction "2_2") (pintype "passive"))
      (node (ref "C13") (pin "2") (pinfunction "2_2") (pintype "passive"))
      (node (ref "C14") (pin "2") (pinfunction "2_2") (pintype "passive"))
      (node (ref "C15") (pin "-") (pinfunction "-_-") (pintype "passive"))
      (node (ref "C16") (pin "2") (pinfunction "2_2") (pintype "passive"))
      (node (ref "C17") (pin "-") (pinfunction "-_-") (pintype "passive"))
      (node (ref "C18") (pin "2") (pinfunction "2_2") (pintype "passive"))
      (node (ref "C2") (pin "2") (pinfunction "-_2") (pintype "passive"))
      (node (ref "C23") (pin "2") (pinfunction "2_2") (pintype "passive"))
      (node (ref "C24") (pin "2") (pinfunction "-_2") (pintype "passive"))
      (node (ref "C25") (pin "2") (pinfunction "2_2") (pintype "passive"))
      (node (ref "C27") (pin "1") (pinfunction "1_1") (pintype "passive"))
      (node (ref "C3") (pin "1") (pinfunction "1_1") (pintype "passive"))
      (node (ref "C4") (pin "-") (pinfunction "-_-") (pintype "passive"))
      (node (ref "C5") (pin "-") (pinfunction "-_-") (pintype "passive"))
      (node (ref "C6") (pin "-") (pinfunction "-_-") (pintype "passive"))
      (node (ref "C7") (pin "2") (pinfunction "2_2") (pintype "passive"))
      (node (ref "C8") (pin "-") (pinfunction "-_-") (pintype "passive"))
      (node (ref "C9") (pin "2") (pinfunction "2_2") (pintype "passive"))
      (node (ref "D1") (pin "A") (pinfunction "A_A") (pintype "passive"))
      (node (ref "J11") (pin "5") (pinfunction "5_5") (pintype "passive"))
      (node (ref "J12") (pin "2") (pinfunction "2_2") (pintype "passive"))
      (node (ref "J13") (pin "3") (pinfunction "3_3") (pintype "passive"))
      (node (ref "J14") (pin "2") (pinfunction "2_2") (pintype "passive"))
      (node (ref "J15") (pin "2") (pinfunction "2_2") (pintype "passive"))
      (node (ref "J15") (pin "4") (pinfunction "4_4") (pintype "passive"))
      (node (ref "J16") (pin "3") (pinfunction "3_3") (pintype "passive"))
      (node (ref "J20") (pin "1") (pinfunction "1_1") (pintype "passive"))
      (node (ref "J20") (pin "10") (pinfunction "10_10") (pintype "passive"))
      (node (ref "J20") (pin "13") (pinfunction "13_13") (pintype "passive"))
      (node (ref "J20") (pin "16") (pinfunction "16_16") (pintype "passive"))
      (node (ref "J20") (pin "19") (pinfunction "19_19") (pintype "passive"))
      (node (ref "J20") (pin "22") (pinfunction "22_22") (pintype "passive"))
      (node (ref "J20") (pin "25") (pinfunction "25_25") (pintype "passive"))
      (node (ref "J20") (pin "28") (pinfunction "28_28") (pintype "passive"))
      (node (ref "J20") (pin "31") (pinfunction "31_31") (pintype "passive"))
      (node (ref "J20") (pin "34") (pinfunction "34_34") (pintype "passive"))
      (node (ref "J20") (pin "37") (pinfunction "37_37") (pintype "passive"))
      (node (ref "J20") (pin "4") (pinfunction "4_4") (pintype "passive"))
      (node (ref "J20") (pin "40") (pinfunction "40_40") (pintype "passive"))
      (node (ref "J20") (pin "43") (pinfunction "43_43") (pintype "passive"))
      (node (ref "J20") (pin "46") (pinfunction "46_46") (pintype "passive"))
      (node (ref "J20") (pin "49") (pinfunction "49_49") (pintype "passive"))
      (node (ref "J20") (pin "7") (pinfunction "7_7") (pintype "passive"))
      (node (ref "J3") (pin "16") (pinfunction "16_16") (pintype "passive"))
      (node (ref "J3") (pin "2") (pinfunction "2_2") (pintype "passive"))
      (node (ref "J4") (pin "5") (pinfunction "5_5") (pintype "passive"))
      (node (ref "J5") (pin "2") (pinfunction "2_2") (pintype "passive"))
      (node (ref "J6") (pin "12") (pinfunction "12_12") (pintype "passive"))
      (node (ref "J6") (pin "15") (pinfunction "15_15") (pintype "passive"))
      (node (ref "J6") (pin "18") (pinfunction "18_18") (pintype "passive"))
      (node (ref "J6") (pin "21") (pinfunction "21_21") (pintype "passive"))
      (node (ref "J6") (pin "24") (pinfunction "24_24") (pintype "passive"))
      (node (ref "J6") (pin "27") (pinfunction "27_27") (pintype "passive"))
      (node (ref "J6") (pin "3") (pinfunction "3_3") (pintype "passive"))
      (node (ref "J6") (pin "30") (pinfunction "30_30") (pintype "passive"))
      (node (ref "J6") (pin "33") (pinfunction "33_33") (pintype "passive"))
      (node (ref "J6") (pin "36") (pinfunction "36_36") (pintype "passive"))
      (node (ref "J6") (pin "39") (pinfunction "39_39") (pintype "passive"))
      (node (ref "J6") (pin "42") (pinfunction "42_42") (pintype "passive"))
      (node (ref "J6") (pin "45") (pinfunction "45_45") (pintype "passive"))
      (node (ref "J6") (pin "48") (pinfunction "48_48") (pintype "passive"))
      (node (ref "J6") (pin "51") (pinfunction "51_51") (pintype "passive"))
      (node (ref "J6") (pin "6") (pinfunction "6_6") (pintype "passive"))
      (node (ref "J6") (pin "9") (pinfunction "9_9") (pintype "passive"))
      (node (ref "J7") (pin "3") (pinfunction "3_3") (pintype "passive"))
      (node (ref "J8") (pin "10") (pinfunction "10_10") (pintype "passive"))
      (node (ref "R23") (pin "1") (pinfunction "1_1") (pintype "passive"))
      (node (ref "U1") (pin "2") (pinfunction "GND_2") (pintype "bidirectional"))
      (node (ref "U11") (pin "1") (pinfunction "GND_1") (pintype "bidirectional"))
      (node (ref "U14") (pin "20") (pinfunction "AVSS_20") (pintype "power_in"))
      (node (ref "U14") (pin "25") (pinfunction "VSS_25") (pintype "power_in"))
      (node (ref "U14") (pin "41") (pinfunction "VSS_41") (pintype "power_in"))
      (node (ref "U14") (pin "56") (pinfunction "VSS_56") (pintype "power_in"))
      (node (ref "U14") (pin "9") (pinfunction "VSS_9") (pintype "power_in"))
      (node (ref "U15") (pin "10") (pinfunction "GND_10") (pintype "power_in"))
      (node (ref "U15") (pin "2") (pinfunction "RTRY_2") (pintype "input"))
      (node (ref "U15") (pin "8") (pinfunction "LSS_8") (pintype "output"))
      (node (ref "U15") (pin "PAD") (pinfunction "PAD_PAD") (pintype "output"))
      (node (ref "U2") (pin "3") (pinfunction "GND_3") (pintype "bidirectional"))
      (node (ref "U2") (pin "5") (pinfunction "SD_5") (pintype "bidirectional"))
      (node (ref "U2") (pin "6") (pinfunction "GND_6") (pintype "bidirectional"))
      (node (ref "U3") (pin "10") (pinfunction "GND_10") (pintype "power_in"))
      (node (ref "U3") (pin "2") (pinfunction "RTRY_2") (pintype "input"))
      (node (ref "U3") (pin "8") (pinfunction "LSS_8") (pintype "output"))
      (node (ref "U3") (pin "PAD") (pinfunction "PAD_PAD") (pintype "output"))
      (node (ref "U4") (pin "10") (pinfunction "GND_10") (pintype "power_in"))
      (node (ref "U4") (pin "2") (pinfunction "RTRY_2") (pintype "input"))
      (node (ref "U4") (pin "8") (pinfunction "LSS_8") (pintype "output"))
      (node (ref "U4") (pin "PAD") (pinfunction "PAD_PAD") (pintype "output"))
      (node (ref "U5") (pin "10") (pinfunction "GND_10") (pintype "power_in"))
      (node (ref "U5") (pin "2") (pinfunction "RTRY_2") (pintype "input"))
      (node (ref "U5") (pin "8") (pinfunction "LSS_8") (pintype "output"))
      (node (ref "U5") (pin "PAD") (pinfunction "PAD_PAD") (pintype "output"))
      (node (ref "U9") (pin "1") (pinfunction "GND_1") (pintype "bidirectional"))
    )
    (net (code "85") (name "Net-(D2-A)") (class "Default")
      (node (ref "D2") (pin "2") (pinfunction "A_2") (pintype "passive"))
      (node (ref "J5") (pin "1") (pinfunction "1_1") (pintype "passive"))
    )
    (net (code "86") (name "Net-(D4-A)") (class "Default")
      (node (ref "D4") (pin "2") (pinfunction "A_2") (pintype "passive"))
      (node (ref "J20") (pin "14") (pinfunction "14_14") (pintype "passive"))
    )
    (net (code "87") (name "Net-(D4-C)") (class "Default")
      (node (ref "D4") (pin "1") (pinfunction "C_1") (pintype "passive"))
      (node (ref "J20") (pin "11") (pinfunction "11_11") (pintype "passive"))
      (node (ref "J20") (pin "2") (pinfunction "2_2") (pintype "passive"))
      (node (ref "J20") (pin "5") (pinfunction "5_5") (pintype "passive"))
      (node (ref "J20") (pin "8") (pinfunction "8_8") (pintype "passive"))
    )
    (net (code "88") (name "Net-(D6-A)") (class "Default")
      (node (ref "D6") (pin "2") (pinfunction "A_2") (pintype "passive"))
      (node (ref "J6") (pin "14") (pinfunction "14_14") (pintype "passive"))
    )
    (net (code "89") (name "Net-(D6-C)") (class "Default")
      (node (ref "D6") (pin "1") (pinfunction "C_1") (pintype "passive"))
      (node (ref "J6") (pin "11") (pinfunction "11_11") (pintype "passive"))
      (node (ref "J6") (pin "2") (pinfunction "2_2") (pintype "passive"))
      (node (ref "J6") (pin "5") (pinfunction "5_5") (pintype "passive"))
      (node (ref "J6") (pin "8") (pinfunction "8_8") (pintype "passive"))
    )
    (net (code "90") (name "Net-(LED1-PadC)") (class "Default")
      (node (ref "LED1") (pin "C") (pinfunction "C_C") (pintype "passive"))
      (node (ref "R19") (pin "1") (pinfunction "1_1") (pintype "passive"))
    )
    (net (code "91") (name "Net-(U2-FB)") (class "Default")
      (node (ref "R22") (pin "1") (pinfunction "1_1") (pintype "passive"))
      (node (ref "R23") (pin "2") (pinfunction "2_2") (pintype "passive"))
      (node (ref "U2") (pin "4") (pinfunction "FB_4") (pintype "bidirectional"))
    )
    (net (code "92") (name "Net-(U2-OUT)") (class "Default")
      (node (ref "D1") (pin "C") (pinfunction "C_C") (pintype "passive"))
      (node (ref "L1") (pin "1") (pinfunction "1_1") (pintype "passive"))
      (node (ref "U2") (pin "2") (pinfunction "OUT_2") (pintype "bidirectional"))
    )
    (net (code "93") (name "Net-(U3-OUT1)") (class "Default")
      (node (ref "J2") (pin "3") (pinfunction "3_3") (pintype "passive"))
      (node (ref "U3") (pin "7") (pinfunction "OUT1_7") (pintype "output"))
    )
    (net (code "94") (name "Net-(U3-OUT2)") (class "Default")
      (node (ref "J2") (pin "4") (pinfunction "4_4") (pintype "passive"))
      (node (ref "U3") (pin "9") (pinfunction "OUT2_9") (pintype "input"))
    )
    (net (code "95") (name "Net-(U4-OUT1)") (class "Default")
      (node (ref "J1") (pin "2") (pinfunction "2_2") (pintype "passive"))
      (node (ref "U4") (pin "7") (pinfunction "OUT1_7") (pintype "output"))
    )
    (net (code "96") (name "Net-(U4-OUT2)") (class "Default")
      (node (ref "J1") (pin "1") (pinfunction "1_1") (pintype "passive"))
      (node (ref "U4") (pin "9") (pinfunction "OUT2_9") (pintype "input"))
    )
    (net (code "97") (name "Net-(U5-OUT1)") (class "Default")
      (node (ref "J1") (pin "4") (pinfunction "4_4") (pintype "passive"))
      (node (ref "U5") (pin "7") (pinfunction "OUT1_7") (pintype "output"))
    )
    (net (code "98") (name "Net-(U5-OUT2)") (class "Default")
      (node (ref "J1") (pin "3") (pinfunction "3_3") (pintype "passive"))
      (node (ref "U5") (pin "9") (pinfunction "OUT2_9") (pintype "input"))
    )
    (net (code "99") (name "Net-(U9-EN)") (class "Default")
      (node (ref "C27") (pin "2") (pinfunction "2_2") (pintype "passive"))
      (node (ref "R32") (pin "1") (pinfunction "1_1") (pintype "passive"))
      (node (ref "U9") (pin "7") (pinfunction "VR2_7") (pintype "bidirectional"))
      (node (ref "U9") (pin "8") (pinfunction "EN_8") (pintype "input"))
    )
    (net (code "100") (name "Net-(U14-AVDD)") (class "Default")
      (node (ref "C9") (pin "1") (pinfunction "1_1") (pintype "passive"))
      (node (ref "R1") (pin "2") (pinfunction "2_2") (pintype "passive"))
      (node (ref "U14") (pin "19") (pinfunction "AVDD_19") (pintype "power_in"))
    )
    (net (code "101") (name "Net-(U14-VDDCORE{slash}VCAP)") (class "Default")
      (node (ref "C3") (pin "2") (pinfunction "2_2") (pintype "passive"))
      (node (ref "U14") (pin "10") (pinfunction "VDDCORE/VCAP_10") (pintype "power_in"))
    )
    (net (code "102") (name "Net-(U15-OUT1)") (class "Default")
      (node (ref "J2") (pin "1") (pinfunction "1_1") (pintype "passive"))
      (node (ref "U15") (pin "7") (pinfunction "OUT1_7") (pintype "output"))
    )
    (net (code "103") (name "Net-(U15-OUT2)") (class "Default")
      (node (ref "J2") (pin "2") (pinfunction "2_2") (pintype "passive"))
      (node (ref "U15") (pin "9") (pinfunction "OUT2_9") (pintype "input"))
    )
    (net (code "104") (name "unconnected-(J12-Pad1)") (class "Default")
      (node (ref "J12") (pin "1") (pinfunction "1_1") (pintype "passive"))
    )
    (net (code "105") (name "unconnected-(J14-Pad1)") (class "Default")
      (node (ref "J14") (pin "1") (pinfunction "1_1") (pintype "passive"))
    )
    (net (code "106") (name "unconnected-(U$1-1-PadP$2)") (class "Default")
      (node (ref "U$1") (pin "P$2") (pinfunction "1_P$2") (pintype "bidirectional"))
    )
    (net (code "107") (name "unconnected-(U$2-1-PadP$2)") (class "Default")
      (node (ref "U$2") (pin "P$2") (pinfunction "1_P$2") (pintype "bidirectional"))
    )
    (net (code "108") (name "unconnected-(U$7-1-PadP$2)") (class "Default")
      (node (ref "U$7") (pin "P$2") (pinfunction "1_P$2") (pintype "bidirectional"))
    )
    (net (code "109") (name "unconnected-(U$8-1-PadP$2)") (class "Default")
      (node (ref "U$8") (pin "P$2") (pinfunction "1_P$2") (pintype "bidirectional"))
    )
    (net (code "110") (name "unconnected-(U3-FAULT-Pad1)") (class "Default")
      (node (ref "U3") (pin "1") (pinfunction "FAULT_1") (pintype "output"))
    )
    (net (code "111") (name "unconnected-(U4-FAULT-Pad1)") (class "Default")
      (node (ref "U4") (pin "1") (pinfunction "FAULT_1") (pintype "output"))
    )
    (net (code "112") (name "unconnected-(U5-FAULT-Pad1)") (class "Default")
      (node (ref "U5") (pin "1") (pinfunction "FAULT_1") (pintype "output"))
    )
    (net (code "113") (name "unconnected-(U9-SDA1-Pad4)") (class "Default")
      (node (ref "U9") (pin "4") (pinfunction "SDA1_4") (pintype "bidirectional"))
    )
    (net (code "114") (name "unconnected-(U14-RE0{slash}~{RD{slash}}P2D-Pad2)") (class "Default")
      (node (ref "U14") (pin "2") (pinfunction "RE0/~{RD/}P2D_2") (pintype "bidirectional"))
    )
    (net (code "115") (name "unconnected-(U14-RE1{slash}~{WR{slash}}P2C-Pad1)") (class "Default")
      (node (ref "U14") (pin "1") (pinfunction "RE1/~{WR/}P2C_1") (pintype "bidirectional"))
    )
    (net (code "116") (name "unconnected-(U14-RG0{slash}ECCP3{slash}P3A-Pad3)") (class "Default")
      (node (ref "U14") (pin "3") (pinfunction "RG0/ECCP3/P3A_3") (pintype "bidirectional"))
    )
    (net (code "117") (name "unconnected-(U15-FAULT-Pad1)") (class "Default")
      (node (ref "U15") (pin "1") (pinfunction "FAULT_1") (pintype "output"))
    )
  )
)
